# 15_USB.net
KiCad netlist of a schematic drawn in Altium Designer
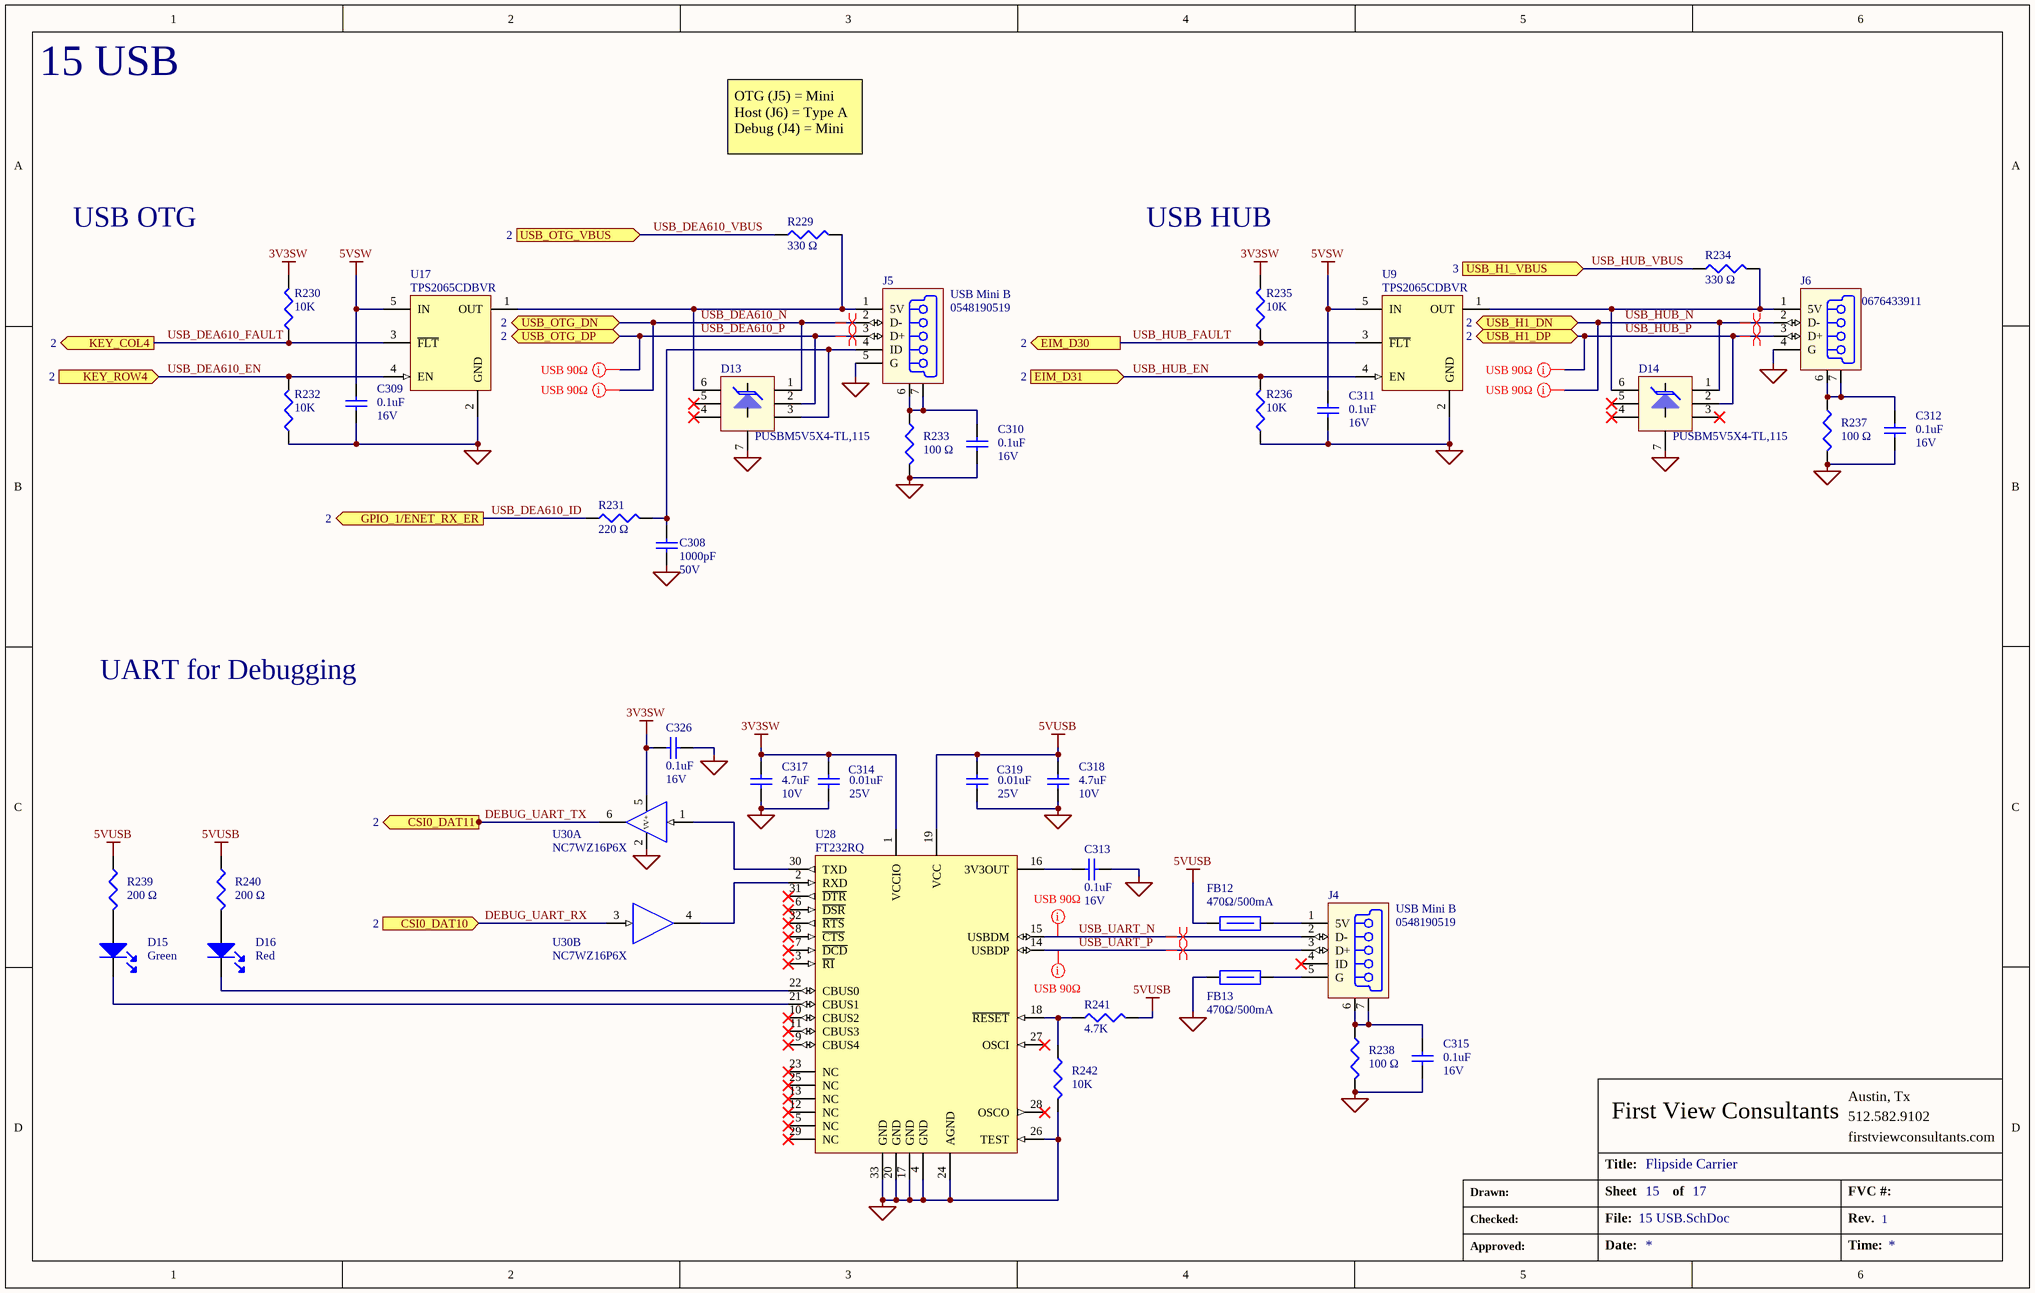
[diagram p0: 15 USB.SchDoc]

(export (version "E")
  (design (tool "Eeschema 10.0.6"))
  (components
    (comp (ref "C308")
      (value "1000pF")
      (footprint "CAP_0402")
      (description "Cap, Cer, 1000pF, 50V, 20%, X7R, 0402")
      (fields
        (field (name "TOLERANCE") "20%")
        (field (name "MANUFACTURER") "Murata Electronics North America")
        (field (name "VOLTAGE") "50V")
      )
      (libsource (lib "Firstview") (part "Cap 1000pF 50V 0402"))
    )
    (comp (ref "C309")
      (value "0.1uF")
      (footprint "CAP_0402")
      (description "Cap, Cer, 0.1uF, 16V, 10%, X7R, 0402")
      (fields
        (field (name "TOLERANCE") "±10%")
        (field (name "MANUFACTURER") "Murata Electronics North America")
        (field (name "VOLTAGE") "16V")
      )
      (libsource (lib "Firstview") (part "Cap 0.1uF 16V 0402"))
    )
    (comp (ref "C310")
      (value "0.1uF")
      (footprint "CAP_0402")
      (description "Cap, Cer, 0.1uF, 16V, 10%, X7R, 0402")
      (fields
        (field (name "TOLERANCE") "±10%")
        (field (name "MANUFACTURER") "Murata Electronics North America")
        (field (name "VOLTAGE") "16V")
      )
      (libsource (lib "Firstview") (part "Cap 0.1uF 16V 0402"))
    )
    (comp (ref "C311")
      (value "0.1uF")
      (footprint "CAP_0402")
      (description "Cap, Cer, 0.1uF, 16V, 10%, X7R, 0402")
      (fields
        (field (name "TOLERANCE") "±10%")
        (field (name "MANUFACTURER") "Murata Electronics North America")
        (field (name "VOLTAGE") "16V")
      )
      (libsource (lib "Firstview") (part "Cap 0.1uF 16V 0402"))
    )
    (comp (ref "C312")
      (value "0.1uF")
      (footprint "CAP_0402")
      (description "Cap, Cer, 0.1uF, 16V, 10%, X7R, 0402")
      (fields
        (field (name "TOLERANCE") "±10%")
        (field (name "MANUFACTURER") "Murata Electronics North America")
        (field (name "VOLTAGE") "16V")
      )
      (libsource (lib "Firstview") (part "Cap 0.1uF 16V 0402"))
    )
    (comp (ref "C313")
      (value "0.1uF")
      (footprint "CAP_0402")
      (description "Cap, Cer, 0.1uF, 16V, 10%, X7R, 0402")
      (fields
        (field (name "TOLERANCE") "±10%")
        (field (name "MANUFACTURER") "Murata Electronics North America")
        (field (name "VOLTAGE") "16V")
      )
      (libsource (lib "Firstview") (part "Cap 0.1uF 16V 0402"))
    )
    (comp (ref "C314")
      (value "0.01uF")
      (footprint "CAP_0402")
      (description "Cap, Cer, 0.01uF, 25V, ±10%, X7R, 0402")
      (fields
        (field (name "TOLERANCE") "±10%")
        (field (name "MANUFACTURER") "Murata")
        (field (name "VOLTAGE") "25V")
      )
      (libsource (lib "Firstview") (part "Cap 0.01uF 50V 0402"))
    )
    (comp (ref "C315")
      (value "0.1uF")
      (footprint "CAP_0402")
      (description "Cap, Cer, 0.1uF, 16V, 10%, X7R, 0402")
      (fields
        (field (name "TOLERANCE") "±10%")
        (field (name "MANUFACTURER") "Murata Electronics North America")
        (field (name "VOLTAGE") "16V")
      )
      (libsource (lib "Firstview") (part "Cap 0.1uF 16V 0402"))
    )
    (comp (ref "C317")
      (value "4.7uF")
      (footprint "CAP_0402")
      (description "Cap, Cer, 4.7uF, 10V, 10%, X5R, 0603")
      (fields
        (field (name "TOLERANCE") "±10%")
        (field (name "VOLTAGE") "10V")
        (field (name "MANUFACTURER") "Taiyo Yuden")
      )
      (libsource (lib "Firstview") (part "Cap 4.7uF 10V 0603"))
    )
    (comp (ref "C318")
      (value "4.7uF")
      (footprint "CAP_0402")
      (description "Cap, Cer, 4.7uF, 10V, 10%, X5R, 0603")
      (fields
        (field (name "TOLERANCE") "±10%")
        (field (name "VOLTAGE") "10V")
        (field (name "MANUFACTURER") "Taiyo Yuden")
      )
      (libsource (lib "Firstview") (part "Cap 4.7uF 10V 0603"))
    )
    (comp (ref "C319")
      (value "0.01uF")
      (footprint "CAP_0402")
      (description "Cap, Cer, 0.01uF, 25V, ±10%, X7R, 0402")
      (fields
        (field (name "TOLERANCE") "±10%")
        (field (name "MANUFACTURER") "Murata")
        (field (name "VOLTAGE") "25V")
      )
      (libsource (lib "Firstview") (part "Cap 0.01uF 50V 0402"))
    )
    (comp (ref "C326")
      (value "0.1uF")
      (footprint "CAP_0402")
      (description "Cap, Cer, 0.1uF, 16V, 10%, X7R, 0402")
      (fields
        (field (name "TOLERANCE") "±10%")
        (field (name "MANUFACTURER") "Murata Electronics North America")
        (field (name "VOLTAGE") "16V")
      )
      (libsource (lib "Firstview") (part "Cap 0.1uF 16V 0402"))
    )
    (comp (ref "D13")
      (value "PUSBM5V5X4-TL,115")
      (footprint "DFN_PUSBM5V5X4-TL,115")
      (description "Diode, TVS, USB 2.0 & OTG, DFN-6")
      (fields (field (name "MANUFACTURER") "NXP Semiconductors"))
      (libsource (lib "Firstview") (part "PUSBM5V5X4-TL,115"))
    )
    (comp (ref "D14")
      (value "PUSBM5V5X4-TL,115")
      (footprint "DFN_PUSBM5V5X4-TL,115")
      (description "Diode, TVS, USB 2.0 & OTG, DFN-6")
      (fields (field (name "MANUFACTURER") "NXP Semiconductors"))
      (libsource (lib "Firstview") (part "PUSBM5V5X4-TL,115"))
    )
    (comp (ref "D15")
      (value "Green")
      (footprint "LED_0603")
      (description "Led, Green, 2mA, 1.7V, 0603")
      (fields
        (field (name "MANUFACTURER") "OSRAM Opto Semiconductors Inc")
        (field (name "Comment") "LG L29K-G2J1-24-Z")
      )
      (libsource (lib "Firstview") (part "LG L29K-G2J1-24-Z"))
    )
    (comp (ref "D16")
      (value "Red")
      (footprint "LED_0603")
      (description "Led, Red, 20mA, 2V, 0603")
      (fields (field (name "MANUFACTURER") "Lite-On Inc") (field (name "Comment") "LTST-C191KRKT"))
      (libsource (lib "Firstview") (part "LTST-C191KRKT"))
    )
    (comp (ref "FB12")
      (value "470Ω/500mA")
      (footprint "IND_0603")
      (description "Ind, Ferrite Bead, 470R, 210mOhm, 0.5A, 0603")
      (fields
        (field (name "MANUFACTURER") "Murata Electronics North America")
        (field (name "Comment") "BLM18EG471SN1D")
      )
      (libsource (lib "Firstview") (part "BLM18EG471SN1D"))
    )
    (comp (ref "FB13")
      (value "470Ω/500mA")
      (footprint "IND_0603")
      (description "Ind, Ferrite Bead, 470R, 210mOhm, 0.5A, 0603")
      (fields
        (field (name "MANUFACTURER") "Murata Electronics North America")
        (field (name "Comment") "BLM18EG471SN1D")
      )
      (libsource (lib "Firstview") (part "BLM18EG471SN1D"))
    )
    (comp (ref "J4")
      (value "0548190519")
      (footprint "CON_USB_0548190519")
      (description "Conn, USB, Mini B, 5 Pos, R/A, TH")
      (fields (field (name "MANUFACTURER") "Molex Inc") (field (name "ALTIUM_VALUE") "USB Mini B"))
      (libsource (lib "Firstview") (part "0548190519"))
    )
    (comp (ref "J5")
      (value "0548190519")
      (footprint "CON_USB_0548190519")
      (description "Conn, USB, Mini B, 5 Pos, R/A, TH")
      (fields (field (name "MANUFACTURER") "Molex Inc") (field (name "ALTIUM_VALUE") "USB Mini B"))
      (libsource (lib "Firstview") (part "0548190519"))
    )
    (comp (ref "J6")
      (value "0676433911")
      (footprint "CON_USB-0676433911")
      (description "Conn, USB, Type A, 4 Pos, R/A, TH")
      (fields (field (name "MANUFACTURER") "Molex Inc"))
      (libsource (lib "Firstview") (part "0676433911"))
    )
    (comp (ref "R229")
      (value "330 Ω")
      (footprint "RES_0402")
      (description "Res, 330R, 0.063W, 1%, 0402")
      (fields (field (name "MANUFACTURER") "Yageo") (field (name "Comment") "Res 330R 0.063W"))
      (libsource (lib "Firstview") (part "Res 330R 0.063W"))
    )
    (comp (ref "R230")
      (value "10K")
      (footprint "RES_0402")
      (description "Res, 10K, 1/16W, 1%, 0402")
      (fields (field (name "MANUFACTURER") "Yageo") (field (name "Comment") "Res 10K 0.063W"))
      (libsource (lib "Firstview") (part "Res 10K 0.063W"))
    )
    (comp (ref "R231")
      (value "220 Ω")
      (footprint "RES_0402")
      (description "Res, 220R, 0.063W, 5%, 0402")
      (fields
        (field (name "MANUFACTURER") "Stackpole Electronics Inc")
        (field (name "Comment") "Res 220R 0.063W")
      )
      (libsource (lib "Firstview") (part "Res 220R 0.063W"))
    )
    (comp (ref "R232")
      (value "10K")
      (footprint "RES_0402")
      (description "Res, 10K, 1/16W, 1%, 0402")
      (fields (field (name "MANUFACTURER") "Yageo") (field (name "Comment") "Res 10K 0.063W"))
      (libsource (lib "Firstview") (part "Res 10K 0.063W"))
    )
    (comp (ref "R233")
      (value "100 Ω")
      (footprint "RES_0402")
      (description "Res, 100R, 0.063W, 1%, 0402")
      (fields
        (field (name "MANUFACTURER") "Murata Electronics North America")
        (field (name "Comment") "Res 100R 0.063W")
      )
      (libsource (lib "Firstview") (part "Res 100R 0.063W"))
    )
    (comp (ref "R234")
      (value "330 Ω")
      (footprint "RES_0402")
      (description "Res, 330R, 0.063W, 1%, 0402")
      (fields (field (name "MANUFACTURER") "Yageo") (field (name "Comment") "Res 330R 0.063W"))
      (libsource (lib "Firstview") (part "Res 330R 0.063W"))
    )
    (comp (ref "R235")
      (value "10K")
      (footprint "RES_0402")
      (description "Res, 10K, 1/16W, 1%, 0402")
      (fields (field (name "MANUFACTURER") "Yageo") (field (name "Comment") "Res 10K 0.063W"))
      (libsource (lib "Firstview") (part "Res 10K 0.063W"))
    )
    (comp (ref "R236")
      (value "10K")
      (footprint "RES_0402")
      (description "Res, 10K, 1/16W, 1%, 0402")
      (fields (field (name "MANUFACTURER") "Yageo") (field (name "Comment") "Res 10K 0.063W"))
      (libsource (lib "Firstview") (part "Res 10K 0.063W"))
    )
    (comp (ref "R237")
      (value "100 Ω")
      (footprint "RES_0402")
      (description "Res, 100R, 0.063W, 1%, 0402")
      (fields
        (field (name "MANUFACTURER") "Murata Electronics North America")
        (field (name "Comment") "Res 100R 0.063W")
      )
      (libsource (lib "Firstview") (part "Res 100R 0.063W"))
    )
    (comp (ref "R238")
      (value "100 Ω")
      (footprint "RES_0402")
      (description "Res, 100R, 0.063W, 1%, 0402")
      (fields
        (field (name "MANUFACTURER") "Murata Electronics North America")
        (field (name "Comment") "Res 100R 0.063W")
      )
      (libsource (lib "Firstview") (part "Res 100R 0.063W"))
    )
    (comp (ref "R239")
      (value "200 Ω")
      (footprint "RES_0402")
      (description "Res, 200R, 0.063W, 1%, 0402")
      (fields (field (name "MANUFACTURER") "Yageo") (field (name "Comment") "Res 200R 0.063W"))
      (libsource (lib "Firstview") (part "Res 200R 0.063W"))
    )
    (comp (ref "R240")
      (value "200 Ω")
      (footprint "RES_0402")
      (description "Res, 200R, 0.063W, 1%, 0402")
      (fields (field (name "MANUFACTURER") "Yageo") (field (name "Comment") "Res 200R 0.063W"))
      (libsource (lib "Firstview") (part "Res 200R 0.063W"))
    )
    (comp (ref "R241")
      (value "4.7K")
      (footprint "RES_0402")
      (description "Res, 4.70K, 0.063W, 1%, 0402")
      (fields (field (name "MANUFACTURER") "Vishay Dale") (field (name "Comment") "Res 4.7K 0.063W"))
      (libsource (lib "Firstview") (part "Res 4.7K 0.063W"))
    )
    (comp (ref "R242")
      (value "10K")
      (footprint "RES_0402")
      (description "Res, 10K, 1/16W, 1%, 0402")
      (fields (field (name "MANUFACTURER") "Yageo") (field (name "Comment") "Res 10K 0.063W"))
      (libsource (lib "Firstview") (part "Res 10K 0.063W"))
    )
    (comp (ref "U9")
      (value "TPS2065CDBVR")
      (footprint "SOT-23-5_TPS2065CDBVR")
      (description "IC, Power Switch, USB, 1.48A, SOT-23-5")
      (fields (field (name "MANUFACTURER") "Texas Instruments"))
      (libsource (lib "Firstview") (part "TPS2065CDBVR"))
    )
    (comp (ref "U17")
      (value "TPS2065CDBVR")
      (footprint "SOT-23-5_TPS2065CDBVR")
      (description "IC, Power Switch, USB, 1.48A, SOT-23-5")
      (fields (field (name "MANUFACTURER") "Texas Instruments"))
      (libsource (lib "Firstview") (part "TPS2065CDBVR"))
    )
    (comp (ref "U28")
      (value "FT232RQ")
      (footprint "VFQFN-32_FT232RQ")
      (description "IC, USB to UART, 3.3-5.25V, QFN-32")
      (fields (field (name "MANUFACTURER") "FTDI"))
      (libsource (lib "Firstview") (part "FT232RQ"))
    )
    (comp (ref "U30")
      (value "NC7WZ16P6X")
      (footprint "SOT-363_NC7WZ16P6X")
      (description "IC, Buffer, 1.65-5.5V, -40+125°C, SOT-363")
      (fields (field (name "MANUFACTURER") "Fairchild Semiconductor"))
      (libsource (lib "Firstview") (part "NC7WZ16P6X"))
    )
  )
  (nets
    (net (code "1") (name "/DEBUG_UART_RX") (class "Default")
      (node (ref "U30") (pin "3") (pinfunction "A2_3") (pintype "input"))
    )
    (net (code "2") (name "/DEBUG_UART_TX") (class "Default")
      (node (ref "U30") (pin "6") (pinfunction "Y1_6") (pintype "open_collector"))
    )
    (net (code "3") (name "/USB_DEA610_EN") (class "Default")
      (node (ref "R232") (pin "1") (pinfunction "1_1") (pintype "passive"))
      (node (ref "U17") (pin "4") (pinfunction "EN_4") (pintype "input"))
    )
    (net (code "4") (name "/USB_DEA610_FAULT") (class "Default")
      (node (ref "R230") (pin "2") (pinfunction "2_2") (pintype "passive"))
      (node (ref "U17") (pin "3") (pinfunction "~{FLT}_3") (pintype "tri_state"))
    )
    (net (code "5") (name "/USB_DEA610_ID") (class "Default")
      (node (ref "R231") (pin "1") (pinfunction "1_1") (pintype "passive"))
    )
    (net (code "6") (name "/USB_DEA610_N") (class "Default")
      (node (ref "D13") (pin "1") (pinfunction "1_1") (pintype "passive"))
      (node (ref "J5") (pin "2") (pinfunction "D-_2") (pintype "bidirectional"))
    )
    (net (code "7") (name "/USB_DEA610_P") (class "Default")
      (node (ref "D13") (pin "2") (pinfunction "2_2") (pintype "passive"))
      (node (ref "J5") (pin "3") (pinfunction "D+_3") (pintype "bidirectional"))
    )
    (net (code "8") (name "/USB_DEA610_VBUS") (class "Default")
      (node (ref "R229") (pin "1") (pinfunction "1_1") (pintype "passive"))
    )
    (net (code "9") (name "/USB_HUB_EN") (class "Default")
      (node (ref "R236") (pin "1") (pinfunction "1_1") (pintype "passive"))
      (node (ref "U9") (pin "4") (pinfunction "EN_4") (pintype "input"))
    )
    (net (code "10") (name "/USB_HUB_FAULT") (class "Default")
      (node (ref "R235") (pin "2") (pinfunction "2_2") (pintype "passive"))
      (node (ref "U9") (pin "3") (pinfunction "~{FLT}_3") (pintype "tri_state"))
    )
    (net (code "11") (name "/USB_HUB_N") (class "Default")
      (node (ref "D14") (pin "1") (pinfunction "1_1") (pintype "passive"))
      (node (ref "J6") (pin "2") (pinfunction "D-_2") (pintype "bidirectional"))
    )
    (net (code "12") (name "/USB_HUB_P") (class "Default")
      (node (ref "D14") (pin "2") (pinfunction "2_2") (pintype "passive"))
      (node (ref "J6") (pin "3") (pinfunction "D+_3") (pintype "bidirectional"))
    )
    (net (code "13") (name "/USB_HUB_VBUS") (class "Default")
      (node (ref "R234") (pin "1") (pinfunction "1_1") (pintype "passive"))
    )
    (net (code "14") (name "/USB_UART_N") (class "Default")
      (node (ref "J4") (pin "2") (pinfunction "D-_2") (pintype "bidirectional"))
      (node (ref "U28") (pin "15") (pinfunction "USBDM_15") (pintype "bidirectional"))
    )
    (net (code "15") (name "/USB_UART_P") (class "Default")
      (node (ref "J4") (pin "3") (pinfunction "D+_3") (pintype "bidirectional"))
      (node (ref "U28") (pin "14") (pinfunction "USBDP_14") (pintype "bidirectional"))
    )
    (net (code "16") (name "3V3SW") (class "Default")
      (node (ref "C314") (pin "1") (pinfunction "1_1") (pintype "passive"))
      (node (ref "C317") (pin "1") (pinfunction "1_1") (pintype "passive"))
      (node (ref "C326") (pin "1") (pinfunction "1_1") (pintype "passive"))
      (node (ref "R230") (pin "1") (pinfunction "1_1") (pintype "passive"))
      (node (ref "R235") (pin "1") (pinfunction "1_1") (pintype "passive"))
      (node (ref "U28") (pin "1") (pinfunction "VCCIO_1") (pintype "power_in"))
      (node (ref "U30") (pin "5") (pinfunction "V+_5") (pintype "power_in"))
    )
    (net (code "17") (name "5VSW") (class "Default")
      (node (ref "C309") (pin "1") (pinfunction "1_1") (pintype "passive"))
      (node (ref "C311") (pin "1") (pinfunction "1_1") (pintype "passive"))
      (node (ref "U17") (pin "5") (pinfunction "IN_5") (pintype "power_in"))
      (node (ref "U9") (pin "5") (pinfunction "IN_5") (pintype "power_in"))
    )
    (net (code "18") (name "5VUSB") (class "Default")
      (node (ref "C318") (pin "1") (pinfunction "1_1") (pintype "passive"))
      (node (ref "C319") (pin "1") (pinfunction "1_1") (pintype "passive"))
      (node (ref "FB12") (pin "1") (pinfunction "1_1") (pintype "passive"))
      (node (ref "R239") (pin "1") (pinfunction "1_1") (pintype "passive"))
      (node (ref "R240") (pin "1") (pinfunction "1_1") (pintype "passive"))
      (node (ref "R241") (pin "2") (pinfunction "2_2") (pintype "passive"))
      (node (ref "U28") (pin "19") (pinfunction "VCC_19") (pintype "power_in"))
    )
    (net (code "19") (name "GND") (class "Default")
      (node (ref "C308") (pin "2") (pinfunction "2_2") (pintype "passive"))
      (node (ref "C309") (pin "2") (pinfunction "2_2") (pintype "passive"))
      (node (ref "C310") (pin "2") (pinfunction "2_2") (pintype "passive"))
      (node (ref "C311") (pin "2") (pinfunction "2_2") (pintype "passive"))
      (node (ref "C312") (pin "2") (pinfunction "2_2") (pintype "passive"))
      (node (ref "C313") (pin "2") (pinfunction "2_2") (pintype "passive"))
      (node (ref "C314") (pin "2") (pinfunction "2_2") (pintype "passive"))
      (node (ref "C315") (pin "2") (pinfunction "2_2") (pintype "passive"))
      (node (ref "C317") (pin "2") (pinfunction "2_2") (pintype "passive"))
      (node (ref "C318") (pin "2") (pinfunction "2_2") (pintype "passive"))
      (node (ref "C319") (pin "2") (pinfunction "2_2") (pintype "passive"))
      (node (ref "C326") (pin "2") (pinfunction "2_2") (pintype "passive"))
      (node (ref "D13") (pin "7") (pinfunction "7_7") (pintype "passive"))
      (node (ref "D14") (pin "7") (pinfunction "7_7") (pintype "passive"))
      (node (ref "FB13") (pin "1") (pinfunction "1_1") (pintype "passive"))
      (node (ref "J5") (pin "5") (pinfunction "G_5") (pintype "power_in"))
      (node (ref "J6") (pin "4") (pinfunction "G_4") (pintype "passive"))
      (node (ref "R232") (pin "2") (pinfunction "2_2") (pintype "passive"))
      (node (ref "R233") (pin "2") (pinfunction "2_2") (pintype "passive"))
      (node (ref "R236") (pin "2") (pinfunction "2_2") (pintype "passive"))
      (node (ref "R237") (pin "2") (pinfunction "2_2") (pintype "passive"))
      (node (ref "R238") (pin "2") (pinfunction "2_2") (pintype "passive"))
      (node (ref "R242") (pin "2") (pinfunction "2_2") (pintype "passive"))
      (node (ref "U17") (pin "2") (pinfunction "GND_2") (pintype "power_in"))
      (node (ref "U28") (pin "17") (pinfunction "GND_17") (pintype "power_in"))
      (node (ref "U28") (pin "20") (pinfunction "GND_20") (pintype "power_in"))
      (node (ref "U28") (pin "24") (pinfunction "AGND_24") (pintype "power_in"))
      (node (ref "U28") (pin "26") (pinfunction "TEST_26") (pintype "input"))
      (node (ref "U28") (pin "33") (pinfunction "GND_33") (pintype "power_in"))
      (node (ref "U28") (pin "4") (pinfunction "GND_4") (pintype "power_in"))
      (node (ref "U30") (pin "2") (pinfunction "V-_2") (pintype "power_in"))
      (node (ref "U9") (pin "2") (pinfunction "GND_2") (pintype "power_in"))
    )
    (net (code "20") (name "Net-(D15-PadA)") (class "Default")
      (node (ref "D15") (pin "A") (pinfunction "A_A") (pintype "passive"))
      (node (ref "R239") (pin "2") (pinfunction "2_2") (pintype "passive"))
    )
    (net (code "21") (name "Net-(D16-PadA)") (class "Default")
      (node (ref "D16") (pin "A") (pinfunction "A_A") (pintype "passive"))
      (node (ref "R240") (pin "2") (pinfunction "2_2") (pintype "passive"))
    )
    (net (code "22") (name "Net-(J4-5V)") (class "Default")
      (node (ref "FB12") (pin "2") (pinfunction "2_2") (pintype "passive"))
      (node (ref "J4") (pin "1") (pinfunction "5V_1") (pintype "power_in"))
    )
    (net (code "23") (name "Net-(J4-G)") (class "Default")
      (node (ref "FB13") (pin "2") (pinfunction "2_2") (pintype "passive"))
      (node (ref "J4") (pin "5") (pinfunction "G_5") (pintype "power_in"))
    )
    (net (code "24") (name "Net-(J4-S1)") (class "Default")
      (node (ref "C315") (pin "1") (pinfunction "1_1") (pintype "passive"))
      (node (ref "J4") (pin "6") (pinfunction "S1_6") (pintype "passive"))
      (node (ref "J4") (pin "7") (pinfunction "S2_7") (pintype "passive"))
      (node (ref "R238") (pin "1") (pinfunction "1_1") (pintype "passive"))
    )
    (net (code "25") (name "Net-(J5-5V)") (class "Default")
      (node (ref "D13") (pin "6") (pinfunction "6_6") (pintype "passive"))
      (node (ref "J5") (pin "1") (pinfunction "5V_1") (pintype "power_in"))
      (node (ref "R229") (pin "2") (pinfunction "2_2") (pintype "passive"))
      (node (ref "U17") (pin "1") (pinfunction "OUT_1") (pintype "power_in"))
    )
    (net (code "26") (name "Net-(J5-ID)") (class "Default")
      (node (ref "C308") (pin "1") (pinfunction "1_1") (pintype "passive"))
      (node (ref "D13") (pin "3") (pinfunction "3_3") (pintype "passive"))
      (node (ref "J5") (pin "4") (pinfunction "ID_4") (pintype "passive"))
      (node (ref "R231") (pin "2") (pinfunction "2_2") (pintype "passive"))
    )
    (net (code "27") (name "Net-(J5-S1)") (class "Default")
      (node (ref "C310") (pin "1") (pinfunction "1_1") (pintype "passive"))
      (node (ref "J5") (pin "6") (pinfunction "S1_6") (pintype "passive"))
      (node (ref "J5") (pin "7") (pinfunction "S2_7") (pintype "passive"))
      (node (ref "R233") (pin "1") (pinfunction "1_1") (pintype "passive"))
    )
    (net (code "28") (name "Net-(J6-5V)") (class "Default")
      (node (ref "D14") (pin "6") (pinfunction "6_6") (pintype "passive"))
      (node (ref "J6") (pin "1") (pinfunction "5V_1") (pintype "power_in"))
      (node (ref "R234") (pin "2") (pinfunction "2_2") (pintype "passive"))
      (node (ref "U9") (pin "1") (pinfunction "OUT_1") (pintype "power_in"))
    )
    (net (code "29") (name "Net-(J6-S1)") (class "Default")
      (node (ref "C312") (pin "1") (pinfunction "1_1") (pintype "passive"))
      (node (ref "J6") (pin "6") (pinfunction "S1_6") (pintype "passive"))
      (node (ref "J6") (pin "7") (pinfunction "S2_7") (pintype "passive"))
      (node (ref "R237") (pin "1") (pinfunction "1_1") (pintype "passive"))
    )
    (net (code "30") (name "Net-(U28-3V3OUT)") (class "Default")
      (node (ref "C313") (pin "1") (pinfunction "1_1") (pintype "passive"))
      (node (ref "U28") (pin "16") (pinfunction "3V3OUT_16") (pintype "power_in"))
    )
    (net (code "31") (name "Net-(U28-CBUS0)") (class "Default")
      (node (ref "D16") (pin "K") (pinfunction "K_K") (pintype "passive"))
      (node (ref "U28") (pin "22") (pinfunction "CBUS0_22") (pintype "bidirectional"))
    )
    (net (code "32") (name "Net-(U28-CBUS1)") (class "Default")
      (node (ref "D15") (pin "K") (pinfunction "K_K") (pintype "passive"))
      (node (ref "U28") (pin "21") (pinfunction "CBUS1_21") (pintype "bidirectional"))
    )
    (net (code "33") (name "Net-(U28-RXD)") (class "Default")
      (node (ref "U28") (pin "2") (pinfunction "RXD_2") (pintype "input"))
      (node (ref "U30") (pin "4") (pinfunction "Y2_4") (pintype "open_collector"))
    )
    (net (code "34") (name "Net-(U28-TXD)") (class "Default")
      (node (ref "U28") (pin "30") (pinfunction "TXD_30") (pintype "output"))
      (node (ref "U30") (pin "1") (pinfunction "A1_1") (pintype "input"))
    )
    (net (code "35") (name "Net-(U28-~{RESET})") (class "Default")
      (node (ref "R241") (pin "1") (pinfunction "1_1") (pintype "passive"))
      (node (ref "R242") (pin "1") (pinfunction "1_1") (pintype "passive"))
      (node (ref "U28") (pin "18") (pinfunction "~{RESET}_18") (pintype "input"))
    )
    (net (code "36") (name "unconnected-(D13-Pad4)") (class "Default")
      (node (ref "D13") (pin "4") (pinfunction "4_4") (pintype "passive+no_connect"))
    )
    (net (code "37") (name "unconnected-(D13-Pad5)") (class "Default")
      (node (ref "D13") (pin "5") (pinfunction "5_5") (pintype "passive+no_connect"))
    )
    (net (code "38") (name "unconnected-(D14-Pad3)") (class "Default")
      (node (ref "D14") (pin "3") (pinfunction "3_3") (pintype "passive+no_connect"))
    )
    (net (code "39") (name "unconnected-(D14-Pad4)") (class "Default")
      (node (ref "D14") (pin "4") (pinfunction "4_4") (pintype "passive+no_connect"))
    )
    (net (code "40") (name "unconnected-(D14-Pad5)") (class "Default")
      (node (ref "D14") (pin "5") (pinfunction "5_5") (pintype "passive+no_connect"))
    )
    (net (code "41") (name "unconnected-(J4-ID-Pad4)") (class "Default")
      (node (ref "J4") (pin "4") (pinfunction "ID_4") (pintype "passive+no_connect"))
    )
    (net (code "42") (name "unconnected-(U28-CBUS2-Pad10)") (class "Default")
      (node (ref "U28") (pin "10") (pinfunction "CBUS2_10") (pintype "bidirectional+no_connect"))
    )
    (net (code "43") (name "unconnected-(U28-CBUS3-Pad11)") (class "Default")
      (node (ref "U28") (pin "11") (pinfunction "CBUS3_11") (pintype "bidirectional+no_connect"))
    )
    (net (code "44") (name "unconnected-(U28-CBUS4-Pad9)") (class "Default")
      (node (ref "U28") (pin "9") (pinfunction "CBUS4_9") (pintype "bidirectional+no_connect"))
    )
    (net (code "45") (name "unconnected-(U28-NC-Pad5)") (class "Default")
      (node (ref "U28") (pin "5") (pinfunction "NC_5") (pintype "passive+no_connect"))
    )
    (net (code "46") (name "unconnected-(U28-NC-Pad12)") (class "Default")
      (node (ref "U28") (pin "12") (pinfunction "NC_12") (pintype "passive+no_connect"))
    )
    (net (code "47") (name "unconnected-(U28-NC-Pad13)") (class "Default")
      (node (ref "U28") (pin "13") (pinfunction "NC_13") (pintype "passive+no_connect"))
    )
    (net (code "48") (name "unconnected-(U28-NC-Pad23)") (class "Default")
      (node (ref "U28") (pin "23") (pinfunction "NC_23") (pintype "passive+no_connect"))
    )
    (net (code "49") (name "unconnected-(U28-NC-Pad25)") (class "Default")
      (node (ref "U28") (pin "25") (pinfunction "NC_25") (pintype "passive+no_connect"))
    )
    (net (code "50") (name "unconnected-(U28-NC-Pad29)") (class "Default")
      (node (ref "U28") (pin "29") (pinfunction "NC_29") (pintype "passive+no_connect"))
    )
    (net (code "51") (name "unconnected-(U28-OSCI-Pad27)") (class "Default")
      (node (ref "U28") (pin "27") (pinfunction "OSCI_27") (pintype "input+no_connect"))
    )
    (net (code "52") (name "unconnected-(U28-OSCO-Pad28)") (class "Default")
      (node (ref "U28") (pin "28") (pinfunction "OSCO_28") (pintype "output+no_connect"))
    )
    (net (code "53") (name "unconnected-(U28-~{CTS}-Pad8)") (class "Default")
      (node (ref "U28") (pin "8") (pinfunction "~{CTS}_8") (pintype "input+no_connect"))
    )
    (net (code "54") (name "unconnected-(U28-~{DCD}-Pad7)") (class "Default")
      (node (ref "U28") (pin "7") (pinfunction "~{DCD}_7") (pintype "input+no_connect"))
    )
    (net (code "55") (name "unconnected-(U28-~{DSR}-Pad6)") (class "Default")
      (node (ref "U28") (pin "6") (pinfunction "~{DSR}_6") (pintype "input+no_connect"))
    )
    (net (code "56") (name "unconnected-(U28-~{DTR}-Pad31)") (class "Default")
      (node (ref "U28") (pin "31") (pinfunction "~{DTR}_31") (pintype "output+no_connect"))
    )
    (net (code "57") (name "unconnected-(U28-~{RI}-Pad3)") (class "Default")
      (node (ref "U28") (pin "3") (pinfunction "~{RI}_3") (pintype "input+no_connect"))
    )
    (net (code "58") (name "unconnected-(U28-~{RTS}-Pad32)") (class "Default")
      (node (ref "U28") (pin "32") (pinfunction "~{RTS}_32") (pintype "output+no_connect"))
    )
  )
)
